# mcu.net
KiCad netlist of a schematic drawn in Altium Designer
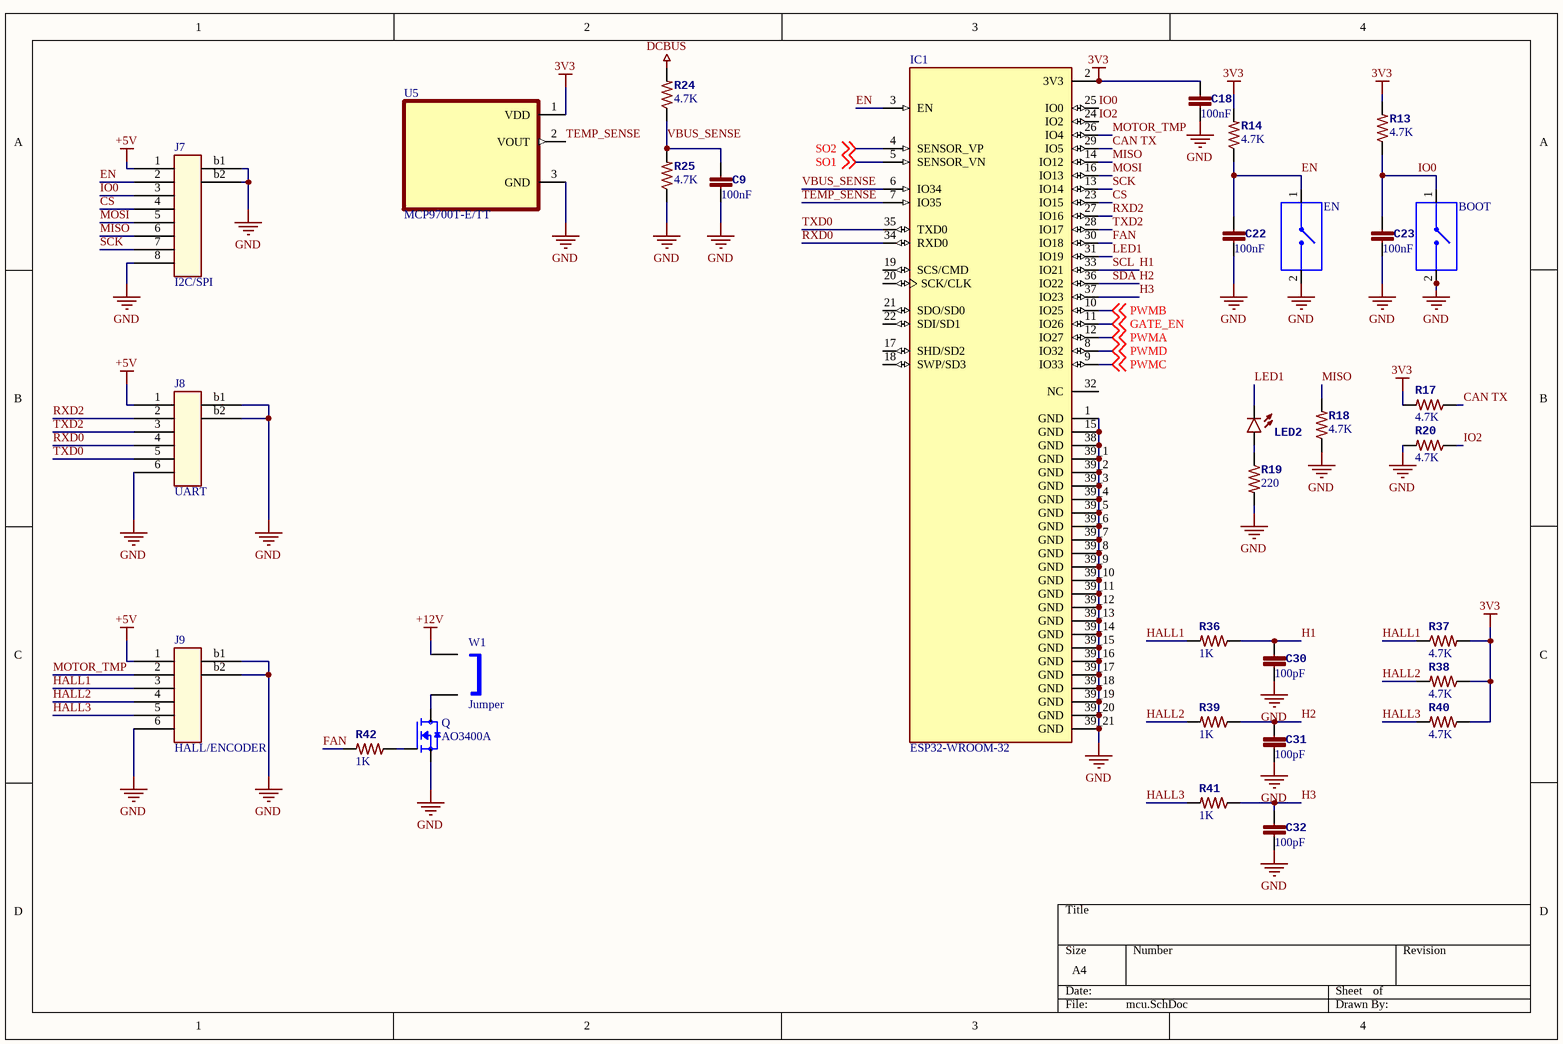
[diagram p0: mcu.SchDoc]

(export (version "E")
  (design (tool "Eeschema 10.0.6"))
  (components
    (comp (ref "BOOT")
      (value "1437566-4")
      (footprint "SW_1437566-4")
      (description "Switch Tactile OFF _ON_ SPST Rectangular Button Gull Wing 0.05A 12VDC 1.77N SMD T/R")
      (fields (field (name "MF") "TE Connectivity") (field (name "DIGI-KEY_PART_NUMBER") "450-1758-1-ND"))
      (libsource (lib "esp_imu_parts") (part "1437566-4"))
    )
    (comp (ref "C9")
      (value "100nF")
      (footprint "_0805")
      (fields (field (name "Comment") "Cap"))
      (libsource (lib "Passives_Integrated_Library") (part "Cap_1"))
    )
    (comp (ref "C18")
      (value "100nF")
      (footprint "_0805")
      (fields (field (name "Comment") "Cap"))
      (libsource (lib "Passives_Integrated_Library") (part "Cap_1"))
    )
    (comp (ref "C22")
      (value "100nF")
      (footprint "_0805")
      (fields (field (name "Comment") "Cap"))
      (libsource (lib "Passives_Integrated_Library") (part "Cap_1"))
    )
    (comp (ref "C23")
      (value "100nF")
      (footprint "_0805")
      (fields (field (name "Comment") "Cap"))
      (libsource (lib "Passives_Integrated_Library") (part "Cap_1"))
    )
    (comp (ref "C30")
      (value "100pF")
      (footprint "_0805")
      (fields (field (name "Comment") "Cap"))
      (libsource (lib "Passives_Integrated_Library") (part "Cap_1"))
    )
    (comp (ref "C31")
      (value "100pF")
      (footprint "_0805")
      (fields (field (name "Comment") "Cap"))
      (libsource (lib "Passives_Integrated_Library") (part "Cap_1"))
    )
    (comp (ref "C32")
      (value "100pF")
      (footprint "_0805")
      (fields (field (name "Comment") "Cap"))
      (libsource (lib "Passives_Integrated_Library") (part "Cap_1"))
    )
    (comp (ref "EN")
      (value "1437566-4")
      (footprint "SW_1437566-4")
      (description "Switch Tactile OFF _ON_ SPST Rectangular Button Gull Wing 0.05A 12VDC 1.77N SMD T/R")
      (fields (field (name "MF") "TE Connectivity") (field (name "DIGI-KEY_PART_NUMBER") "450-1758-1-ND"))
      (libsource (lib "esp_imu_parts") (part "1437566-4"))
    )
    (comp (ref "IC1")
      (value "ESP32-WROOM-32")
      (footprint "MODULE_ESP32-WROOM-32")
      (fields
        (field (name "MF") "Espressif Systems")
        (field (name "DIGI-KEY_PART_NUMBER") "1965-ESP32-WROOM-32U-N4CT-ND")
      )
      (libsource (lib "ESP32-WROOM-32") (part "ESP32-WROOM-32"))
    )
    (comp (ref "J7")
      (value "I2C/SPI")
      (footprint "JST_FH_8P")
      (libsource (lib "Headers_Integrated_Library") (part "JST_FH_8P"))
    )
    (comp (ref "J8")
      (value "UART")
      (footprint "JST_FH_6P")
      (libsource (lib "Headers_Integrated_Library") (part "JST_FH_6P"))
    )
    (comp (ref "J9")
      (value "HALL/ENCODER")
      (footprint "JST_FH_6P")
      (libsource (lib "Headers_Integrated_Library") (part "JST_FH_6P"))
    )
    (comp (ref "LED2")
      (value "LED")
      (footprint "_LED-0805")
      (libsource (lib "Diodes_Integrated_Library") (part "LED"))
    )
    (comp (ref "Q")
      (value "AO3400A")
      (footprint "SOT95P280X125-3N")
      (description "N-Channel 30V 5.7A _Ta_ 1.4W _Ta_ Surface Mount SOT-23-3L")
      (fields (field (name "MF") "Alpha &"))
      (libsource (lib "AO3400A") (part "AO3400A"))
    )
    (comp (ref "R13")
      (value "4.7K")
      (footprint "_0805")
      (fields (field (name "Comment") "Resistor"))
      (libsource (lib "Passives_Integrated_Library") (part "Resistor"))
    )
    (comp (ref "R14")
      (value "4.7K")
      (footprint "_0805")
      (fields (field (name "Comment") "Resistor"))
      (libsource (lib "Passives_Integrated_Library") (part "Resistor"))
    )
    (comp (ref "R17")
      (value "4.7K")
      (footprint "_0805")
      (fields (field (name "Comment") "Resistor"))
      (libsource (lib "Passives_Integrated_Library") (part "Resistor"))
    )
    (comp (ref "R18")
      (value "4.7K")
      (footprint "_0805")
      (fields (field (name "Comment") "Resistor"))
      (libsource (lib "Passives_Integrated_Library") (part "Resistor"))
    )
    (comp (ref "R19")
      (value "220")
      (footprint "_0805")
      (fields (field (name "Comment") "Resistor"))
      (libsource (lib "Passives_Integrated_Library") (part "Resistor"))
    )
    (comp (ref "R20")
      (value "4.7K")
      (footprint "_0805")
      (fields (field (name "Comment") "Resistor"))
      (libsource (lib "Passives_Integrated_Library") (part "Resistor"))
    )
    (comp (ref "R24")
      (value "4.7K")
      (footprint "_0805")
      (fields (field (name "Comment") "Resistor"))
      (libsource (lib "Passives_Integrated_Library") (part "Resistor"))
    )
    (comp (ref "R25")
      (value "4.7K")
      (footprint "_0805")
      (fields (field (name "Comment") "Resistor"))
      (libsource (lib "Passives_Integrated_Library") (part "Resistor"))
    )
    (comp (ref "R36")
      (value "1K")
      (footprint "_0805")
      (fields (field (name "Comment") "Resistor"))
      (libsource (lib "Passives_Integrated_Library") (part "Resistor"))
    )
    (comp (ref "R37")
      (value "4.7K")
      (footprint "_0805")
      (fields (field (name "Comment") "Resistor"))
      (libsource (lib "Passives_Integrated_Library") (part "Resistor"))
    )
    (comp (ref "R38")
      (value "4.7K")
      (footprint "_0805")
      (fields (field (name "Comment") "Resistor"))
      (libsource (lib "Passives_Integrated_Library") (part "Resistor"))
    )
    (comp (ref "R39")
      (value "1K")
      (footprint "_0805")
      (fields (field (name "Comment") "Resistor"))
      (libsource (lib "Passives_Integrated_Library") (part "Resistor"))
    )
    (comp (ref "R40")
      (value "4.7K")
      (footprint "_0805")
      (fields (field (name "Comment") "Resistor"))
      (libsource (lib "Passives_Integrated_Library") (part "Resistor"))
    )
    (comp (ref "R41")
      (value "1K")
      (footprint "_0805")
      (fields (field (name "Comment") "Resistor"))
      (libsource (lib "Passives_Integrated_Library") (part "Resistor"))
    )
    (comp (ref "R42")
      (value "1K")
      (footprint "_0805")
      (fields (field (name "Comment") "Resistor"))
      (libsource (lib "Passives_Integrated_Library") (part "Resistor"))
    )
    (comp (ref "U5")
      (value "MCP9700T-E/TT")
      (footprint "SOT95P237X112-3N")
      (description "Temperature Sensor Analog, Local -40Â°C ~ 125Â°C 10mV/Â°C SOT-23-3")
      (fields (field (name "MF") "Microchip"))
      (libsource (lib "MCP9700T-E_TT") (part "MCP9700T-E/TT"))
    )
    (comp (ref "W1")
      (value "Jumper")
      (footprint "My_IDC-2")
      (description "Jumper Wire")
      (fields (field (name "MANUFACTURER") "Generic Components"))
      (libsource (lib "Others_Integrated_Library") (part "Jumper"))
    )
  )
  (nets
    (net (code "1") (name "+5V") (class "Default")
      (node (ref "J7") (pin "1") (pinfunction "1_1") (pintype "passive"))
      (node (ref "J8") (pin "1") (pinfunction "1_1") (pintype "passive"))
      (node (ref "J9") (pin "1") (pinfunction "1_1") (pintype "passive"))
    )
    (net (code "2") (name "+12V") (class "Default")
      (node (ref "W1") (pin "1") (pinfunction "1_1") (pintype "passive"))
    )
    (net (code "3") (name "/CAN TX") (class "Default")
      (node (ref "IC1") (pin "29") (pinfunction "IO5_29") (pintype "bidirectional"))
      (node (ref "R17") (pin "1") (pinfunction "1_1") (pintype "passive"))
    )
    (net (code "4") (name "/CS") (class "Default")
      (node (ref "IC1") (pin "23") (pinfunction "IO15_23") (pintype "bidirectional"))
      (node (ref "J7") (pin "4") (pinfunction "4_4") (pintype "passive"))
    )
    (net (code "5") (name "/EN") (class "Default")
      (node (ref "C22") (pin "1") (pinfunction "1_1") (pintype "passive"))
      (node (ref "EN") (pin "1") (pinfunction "1_1") (pintype "passive"))
      (node (ref "IC1") (pin "3") (pinfunction "EN_3") (pintype "input"))
      (node (ref "J7") (pin "2") (pinfunction "2_2") (pintype "passive"))
      (node (ref "R14") (pin "1") (pinfunction "1_1") (pintype "passive"))
    )
    (net (code "6") (name "/FAN") (class "Default")
      (node (ref "IC1") (pin "30") (pinfunction "IO18_30") (pintype "bidirectional"))
      (node (ref "R42") (pin "2") (pinfunction "2_2") (pintype "passive"))
    )
    (net (code "7") (name "/H1") (class "Default")
      (node (ref "C30") (pin "1") (pinfunction "1_1") (pintype "passive"))
      (node (ref "IC1") (pin "33") (pinfunction "IO21_33") (pintype "bidirectional"))
      (node (ref "R36") (pin "1") (pinfunction "1_1") (pintype "passive"))
    )
    (net (code "8") (name "/H2") (class "Default")
      (node (ref "C31") (pin "1") (pinfunction "1_1") (pintype "passive"))
      (node (ref "IC1") (pin "36") (pinfunction "IO22_36") (pintype "bidirectional"))
      (node (ref "R39") (pin "1") (pinfunction "1_1") (pintype "passive"))
    )
    (net (code "9") (name "/H3") (class "Default")
      (node (ref "C32") (pin "1") (pinfunction "1_1") (pintype "passive"))
      (node (ref "IC1") (pin "37") (pinfunction "IO23_37") (pintype "bidirectional"))
      (node (ref "R41") (pin "1") (pinfunction "1_1") (pintype "passive"))
    )
    (net (code "10") (name "/HALL1") (class "Default")
      (node (ref "J9") (pin "3") (pinfunction "3_3") (pintype "passive"))
      (node (ref "R36") (pin "2") (pinfunction "2_2") (pintype "passive"))
      (node (ref "R37") (pin "1") (pinfunction "1_1") (pintype "passive"))
    )
    (net (code "11") (name "/HALL2") (class "Default")
      (node (ref "J9") (pin "4") (pinfunction "4_4") (pintype "passive"))
      (node (ref "R38") (pin "2") (pinfunction "2_2") (pintype "passive"))
      (node (ref "R39") (pin "2") (pinfunction "2_2") (pintype "passive"))
    )
    (net (code "12") (name "/HALL3") (class "Default")
      (node (ref "J9") (pin "5") (pinfunction "5_5") (pintype "passive"))
      (node (ref "R40") (pin "2") (pinfunction "2_2") (pintype "passive"))
      (node (ref "R41") (pin "2") (pinfunction "2_2") (pintype "passive"))
    )
    (net (code "13") (name "/IO0") (class "Default")
      (node (ref "BOOT") (pin "1") (pinfunction "1_1") (pintype "passive"))
      (node (ref "C23") (pin "1") (pinfunction "1_1") (pintype "passive"))
      (node (ref "IC1") (pin "25") (pinfunction "IO0_25") (pintype "bidirectional"))
      (node (ref "J7") (pin "3") (pinfunction "3_3") (pintype "passive"))
      (node (ref "R13") (pin "1") (pinfunction "1_1") (pintype "passive"))
    )
    (net (code "14") (name "/IO2") (class "Default")
      (node (ref "IC1") (pin "24") (pinfunction "IO2_24") (pintype "bidirectional"))
      (node (ref "R20") (pin "1") (pinfunction "1_1") (pintype "passive"))
    )
    (net (code "15") (name "/LED1") (class "Default")
      (node (ref "IC1") (pin "31") (pinfunction "IO19_31") (pintype "bidirectional"))
      (node (ref "LED2") (pin "K") (pinfunction "K_K") (pintype "passive"))
    )
    (net (code "16") (name "/MISO") (class "Default")
      (node (ref "IC1") (pin "14") (pinfunction "IO12_14") (pintype "bidirectional"))
      (node (ref "J7") (pin "6") (pinfunction "6_6") (pintype "passive"))
      (node (ref "R18") (pin "2") (pinfunction "2_2") (pintype "passive"))
    )
    (net (code "17") (name "/MOSI") (class "Default")
      (node (ref "IC1") (pin "16") (pinfunction "IO13_16") (pintype "bidirectional"))
      (node (ref "J7") (pin "5") (pinfunction "5_5") (pintype "passive"))
    )
    (net (code "18") (name "/MOTOR_TMP") (class "Default")
      (node (ref "IC1") (pin "26") (pinfunction "IO4_26") (pintype "bidirectional"))
      (node (ref "J9") (pin "2") (pinfunction "2_2") (pintype "passive"))
    )
    (net (code "19") (name "/RXD0") (class "Default")
      (node (ref "IC1") (pin "34") (pinfunction "RXD0_34") (pintype "bidirectional"))
      (node (ref "J8") (pin "4") (pinfunction "4_4") (pintype "passive"))
    )
    (net (code "20") (name "/RXD2") (class "Default")
      (node (ref "IC1") (pin "27") (pinfunction "IO16_27") (pintype "bidirectional"))
      (node (ref "J8") (pin "2") (pinfunction "2_2") (pintype "passive"))
    )
    (net (code "21") (name "/SCK") (class "Default")
      (node (ref "IC1") (pin "13") (pinfunction "IO14_13") (pintype "bidirectional"))
      (node (ref "J7") (pin "7") (pinfunction "7_7") (pintype "passive"))
    )
    (net (code "22") (name "/TEMP_SENSE") (class "Default")
      (node (ref "IC1") (pin "7") (pinfunction "IO35_7") (pintype "input"))
      (node (ref "U5") (pin "2") (pinfunction "VOUT_2") (pintype "output"))
    )
    (net (code "23") (name "/TXD0") (class "Default")
      (node (ref "IC1") (pin "35") (pinfunction "TXD0_35") (pintype "bidirectional"))
      (node (ref "J8") (pin "5") (pinfunction "5_5") (pintype "passive"))
    )
    (net (code "24") (name "/TXD2") (class "Default")
      (node (ref "IC1") (pin "28") (pinfunction "IO17_28") (pintype "bidirectional"))
      (node (ref "J8") (pin "3") (pinfunction "3_3") (pintype "passive"))
    )
    (net (code "25") (name "/VBUS_SENSE") (class "Default")
      (node (ref "C9") (pin "1") (pinfunction "1_1") (pintype "passive"))
      (node (ref "IC1") (pin "6") (pinfunction "IO34_6") (pintype "input"))
      (node (ref "R24") (pin "1") (pinfunction "1_1") (pintype "passive"))
      (node (ref "R25") (pin "2") (pinfunction "2_2") (pintype "passive"))
    )
    (net (code "26") (name "3V3") (class "Default")
      (node (ref "C18") (pin "1") (pinfunction "1_1") (pintype "passive"))
      (node (ref "IC1") (pin "2") (pinfunction "3V3_2") (pintype "power_in"))
      (node (ref "R13") (pin "2") (pinfunction "2_2") (pintype "passive"))
      (node (ref "R14") (pin "2") (pinfunction "2_2") (pintype "passive"))
      (node (ref "R17") (pin "2") (pinfunction "2_2") (pintype "passive"))
      (node (ref "R37") (pin "2") (pinfunction "2_2") (pintype "passive"))
      (node (ref "R38") (pin "1") (pinfunction "1_1") (pintype "passive"))
      (node (ref "R40") (pin "1") (pinfunction "1_1") (pintype "passive"))
      (node (ref "U5") (pin "1") (pinfunction "VDD_1") (pintype "power_in"))
    )
    (net (code "27") (name "DCBUS") (class "Default")
      (node (ref "R24") (pin "2") (pinfunction "2_2") (pintype "passive"))
    )
    (net (code "28") (name "GATE_EN") (class "Default")
      (node (ref "IC1") (pin "11") (pinfunction "IO26_11") (pintype "bidirectional"))
    )
    (net (code "29") (name "GND") (class "Default")
      (node (ref "BOOT") (pin "2") (pinfunction "2_2") (pintype "passive"))
      (node (ref "C18") (pin "2") (pinfunction "2_2") (pintype "passive"))
      (node (ref "C22") (pin "2") (pinfunction "2_2") (pintype "passive"))
      (node (ref "C23") (pin "2") (pinfunction "2_2") (pintype "passive"))
      (node (ref "C30") (pin "2") (pinfunction "2_2") (pintype "passive"))
      (node (ref "C31") (pin "2") (pinfunction "2_2") (pintype "passive"))
      (node (ref "C32") (pin "2") (pinfunction "2_2") (pintype "passive"))
      (node (ref "C9") (pin "2") (pinfunction "2_2") (pintype "passive"))
      (node (ref "EN") (pin "2") (pinfunction "2_2") (pintype "passive"))
      (node (ref "IC1") (pin "1") (pinfunction "GND_1") (pintype "power_in"))
      (node (ref "IC1") (pin "15") (pinfunction "GND_15") (pintype "power_in"))
      (node (ref "IC1") (pin "38") (pinfunction "GND_38") (pintype "power_in"))
      (node (ref "IC1") (pin "39_1") (pinfunction "GND_39_1") (pintype "power_in"))
      (node (ref "IC1") (pin "39_10") (pinfunction "GND_39_10") (pintype "power_in"))
      (node (ref "IC1") (pin "39_11") (pinfunction "GND_39_11") (pintype "power_in"))
      (node (ref "IC1") (pin "39_12") (pinfunction "GND_39_12") (pintype "power_in"))
      (node (ref "IC1") (pin "39_13") (pinfunction "GND_39_13") (pintype "power_in"))
      (node (ref "IC1") (pin "39_14") (pinfunction "GND_39_14") (pintype "power_in"))
      (node (ref "IC1") (pin "39_15") (pinfunction "GND_39_15") (pintype "power_in"))
      (node (ref "IC1") (pin "39_16") (pinfunction "GND_39_16") (pintype "power_in"))
      (node (ref "IC1") (pin "39_17") (pinfunction "GND_39_17") (pintype "power_in"))
      (node (ref "IC1") (pin "39_18") (pinfunction "GND_39_18") (pintype "power_in"))
      (node (ref "IC1") (pin "39_19") (pinfunction "GND_39_19") (pintype "power_in"))
      (node (ref "IC1") (pin "39_2") (pinfunction "GND_39_2") (pintype "power_in"))
      (node (ref "IC1") (pin "39_20") (pinfunction "GND_39_20") (pintype "power_in"))
      (node (ref "IC1") (pin "39_21") (pinfunction "GND_39_21") (pintype "power_in"))
      (node (ref "IC1") (pin "39_3") (pinfunction "GND_39_3") (pintype "power_in"))
      (node (ref "IC1") (pin "39_4") (pinfunction "GND_39_4") (pintype "power_in"))
      (node (ref "IC1") (pin "39_5") (pinfunction "GND_39_5") (pintype "power_in"))
      (node (ref "IC1") (pin "39_6") (pinfunction "GND_39_6") (pintype "power_in"))
      (node (ref "IC1") (pin "39_7") (pinfunction "GND_39_7") (pintype "power_in"))
      (node (ref "IC1") (pin "39_8") (pinfunction "GND_39_8") (pintype "power_in"))
      (node (ref "IC1") (pin "39_9") (pinfunction "GND_39_9") (pintype "power_in"))
      (node (ref "J7") (pin "8") (pinfunction "8_8") (pintype "passive"))
      (node (ref "J7") (pin "b1") (pinfunction "b1_b1") (pintype "passive"))
      (node (ref "J7") (pin "b2") (pinfunction "b2_b2") (pintype "passive"))
      (node (ref "J8") (pin "6") (pinfunction "6_6") (pintype "passive"))
      (node (ref "J8") (pin "b1") (pinfunction "b1_b1") (pintype "passive"))
      (node (ref "J8") (pin "b2") (pinfunction "b2_b2") (pintype "passive"))
      (node (ref "J9") (pin "6") (pinfunction "6_6") (pintype "passive"))
      (node (ref "J9") (pin "b1") (pinfunction "b1_b1") (pintype "passive"))
      (node (ref "J9") (pin "b2") (pinfunction "b2_b2") (pintype "passive"))
      (node (ref "Q") (pin "2") (pinfunction "S_2") (pintype "passive"))
      (node (ref "R18") (pin "1") (pinfunction "1_1") (pintype "passive"))
      (node (ref "R19") (pin "2") (pinfunction "2_2") (pintype "passive"))
      (node (ref "R20") (pin "2") (pinfunction "2_2") (pintype "passive"))
      (node (ref "R25") (pin "1") (pinfunction "1_1") (pintype "passive"))
      (node (ref "U5") (pin "3") (pinfunction "GND_3") (pintype "power_in"))
    )
    (net (code "30") (name "Net-(LED2-PadA)") (class "Default")
      (node (ref "LED2") (pin "A") (pinfunction "A_A") (pintype "passive"))
      (node (ref "R19") (pin "1") (pinfunction "1_1") (pintype "passive"))
    )
    (net (code "31") (name "Net-(Q-D)") (class "Default")
      (node (ref "Q") (pin "3") (pinfunction "D_3") (pintype "passive"))
      (node (ref "W1") (pin "2") (pinfunction "2_2") (pintype "passive"))
    )
    (net (code "32") (name "Net-(Q-G)") (class "Default")
      (node (ref "Q") (pin "1") (pinfunction "G_1") (pintype "passive"))
      (node (ref "R42") (pin "1") (pinfunction "1_1") (pintype "passive"))
    )
    (net (code "33") (name "PWMA") (class "Default")
      (node (ref "IC1") (pin "12") (pinfunction "IO27_12") (pintype "bidirectional"))
    )
    (net (code "34") (name "PWMB") (class "Default")
      (node (ref "IC1") (pin "10") (pinfunction "IO25_10") (pintype "bidirectional"))
    )
    (net (code "35") (name "PWMC") (class "Default")
      (node (ref "IC1") (pin "9") (pinfunction "IO33_9") (pintype "bidirectional"))
    )
    (net (code "36") (name "PWMD") (class "Default")
      (node (ref "IC1") (pin "8") (pinfunction "IO32_8") (pintype "bidirectional"))
    )
    (net (code "37") (name "SO1") (class "Default")
      (node (ref "IC1") (pin "5") (pinfunction "SENSOR_VN_5") (pintype "input"))
    )
    (net (code "38") (name "SO2") (class "Default")
      (node (ref "IC1") (pin "4") (pinfunction "SENSOR_VP_4") (pintype "input"))
    )
    (net (code "39") (name "unconnected-(IC1-NC-Pad32)") (class "Default")
      (node (ref "IC1") (pin "32") (pinfunction "NC_32") (pintype "passive"))
    )
    (net (code "40") (name "unconnected-(IC1-SCK{slash}CLK-Pad20)") (class "Default")
      (node (ref "IC1") (pin "20") (pinfunction "SCK/CLK_20") (pintype "bidirectional"))
    )
    (net (code "41") (name "unconnected-(IC1-SCS{slash}CMD-Pad19)") (class "Default")
      (node (ref "IC1") (pin "19") (pinfunction "SCS/CMD_19") (pintype "bidirectional"))
    )
    (net (code "42") (name "unconnected-(IC1-SDI{slash}SD1-Pad22)") (class "Default")
      (node (ref "IC1") (pin "22") (pinfunction "SDI/SD1_22") (pintype "bidirectional"))
    )
    (net (code "43") (name "unconnected-(IC1-SDO{slash}SD0-Pad21)") (class "Default")
      (node (ref "IC1") (pin "21") (pinfunction "SDO/SD0_21") (pintype "bidirectional"))
    )
    (net (code "44") (name "unconnected-(IC1-SHD{slash}SD2-Pad17)") (class "Default")
      (node (ref "IC1") (pin "17") (pinfunction "SHD/SD2_17") (pintype "bidirectional"))
    )
    (net (code "45") (name "unconnected-(IC1-SWP{slash}SD3-Pad18)") (class "Default")
      (node (ref "IC1") (pin "18") (pinfunction "SWP/SD3_18") (pintype "bidirectional"))
    )
  )
)
